# EBF31A_production_rev_3_1.net
KiCad netlist of a schematic drawn in EAGLE
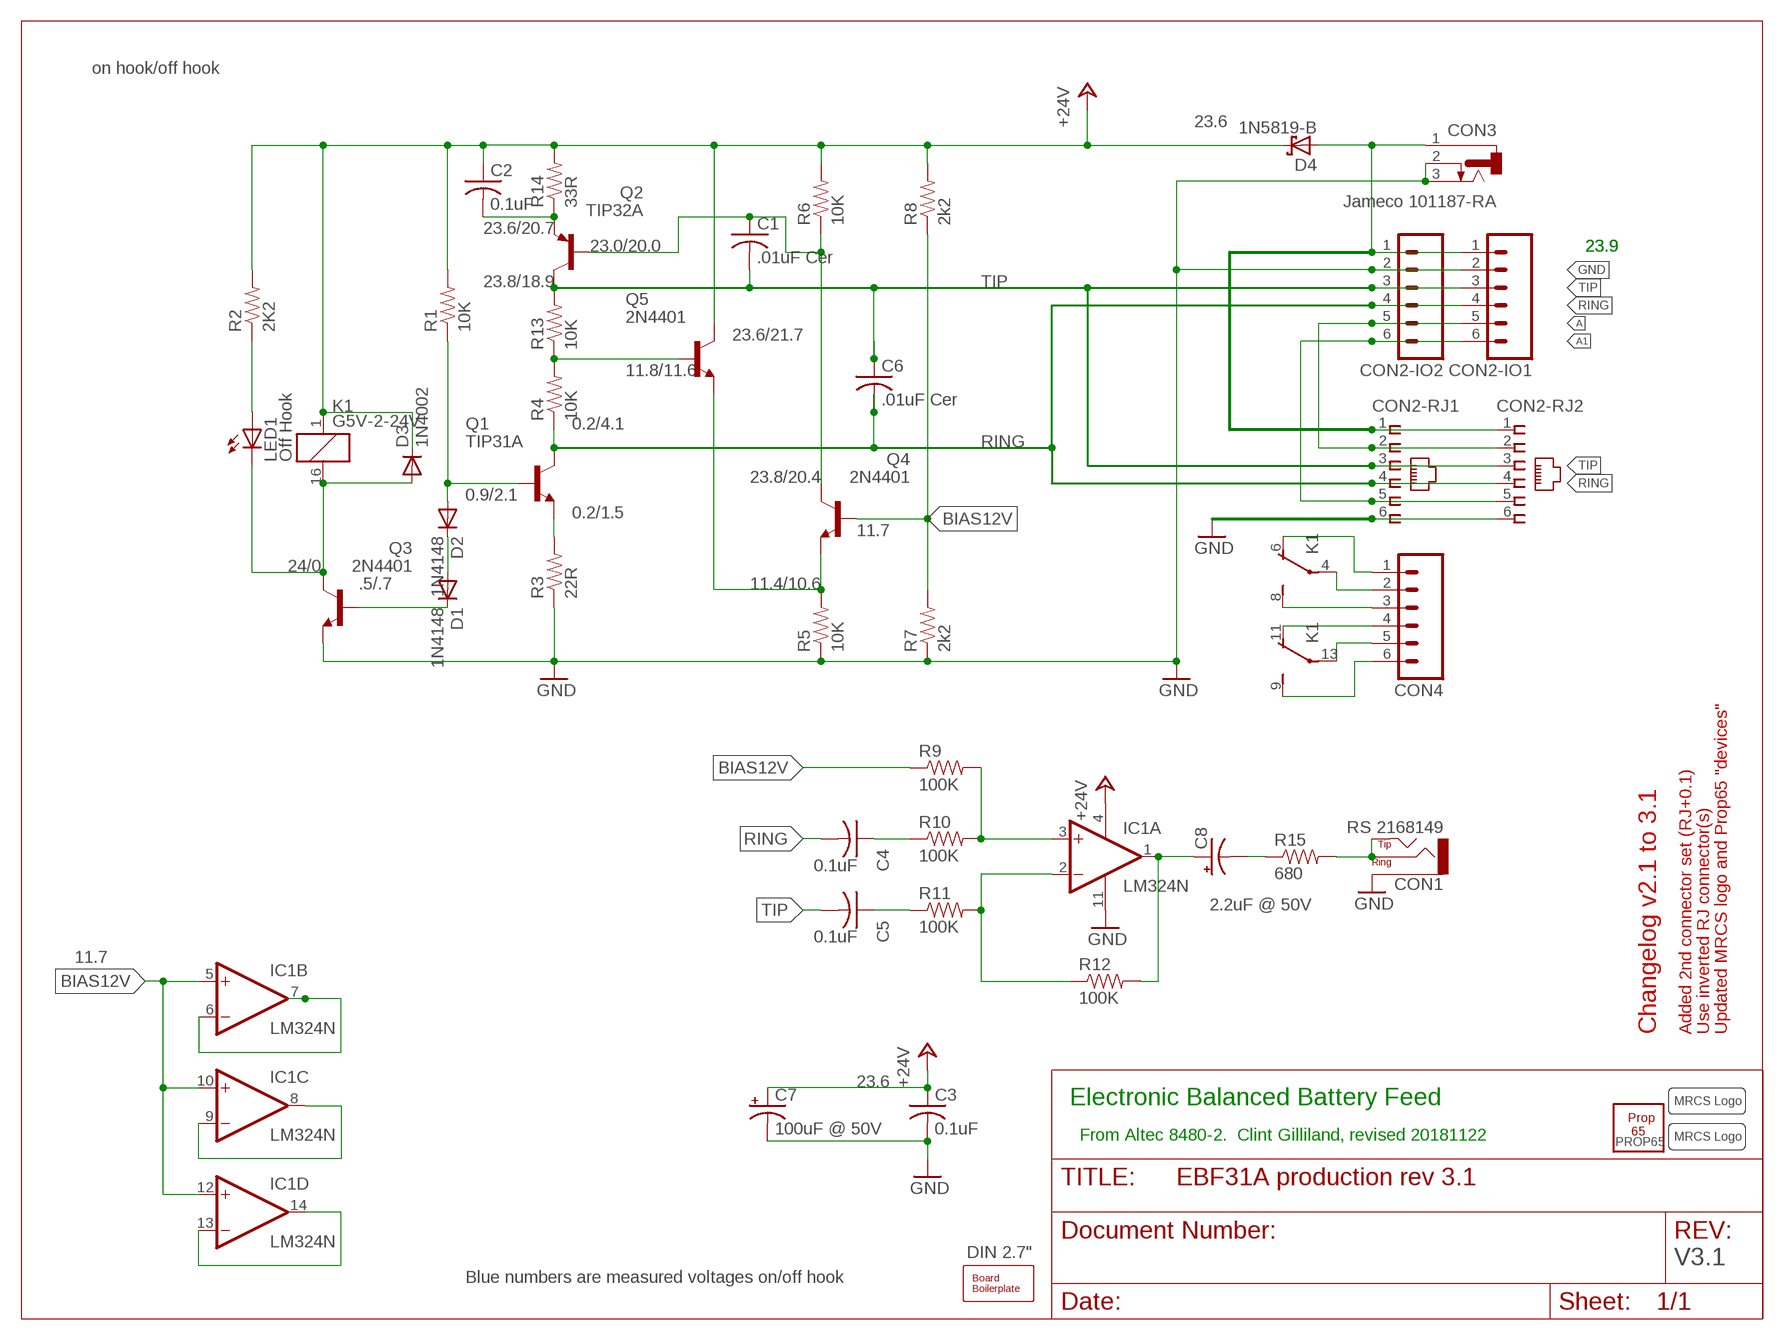
[diagram p0: schematic, sheet 1]

(export (version "E")
  (design (tool "Eeschema 10.0.6"))
  (components
    (comp (ref "C1")
      (value ".01uF Cer")
      (footprint "eagle-import:C025-030X050")
      (libsource (lib "eagle-import") (part "C-US025-030X050"))
    )
    (comp (ref "C2")
      (value "0.1uF")
      (footprint "eagle-import:C025-030X050")
      (libsource (lib "eagle-import") (part "C-US025-030X050"))
    )
    (comp (ref "C3")
      (value "0.1uF")
      (footprint "eagle-import:C025-030X050")
      (libsource (lib "eagle-import") (part "C-US025-030X050"))
    )
    (comp (ref "C4")
      (value "0.1uF")
      (footprint "eagle-import:C025-030X050")
      (libsource (lib "eagle-import") (part "C-US025-030X050"))
    )
    (comp (ref "C5")
      (value "0.1uF")
      (footprint "eagle-import:C025-030X050")
      (libsource (lib "eagle-import") (part "C-US025-030X050"))
    )
    (comp (ref "C6")
      (value ".01uF Cer")
      (footprint "eagle-import:C025-030X050")
      (libsource (lib "eagle-import") (part "C-US025-030X050"))
    )
    (comp (ref "C7")
      (value "100uF @ 50V")
      (footprint "eagle-import:E3,5-10")
      (libsource (lib "eagle-import") (part "CPOL-USE3.5-10"))
    )
    (comp (ref "C8")
      (value "2.2uF @ 50V")
      (footprint "eagle-import:E2-5")
      (libsource (lib "eagle-import") (part "CPOL-USE2-5"))
    )
    (comp (ref "CON1")
      (value "RS 2168149")
      (footprint "eagle-import:AUDIO-JACK-3.5MM_STEREO")
      (libsource (lib "eagle-import") (part "CONNECTOR-AUDIO3.5MM-ADAMTECH"))
    )
    (comp (ref "CON2-IO1")
      (value "M06FEMALE_LOCK")
      (footprint "eagle-import:1X06_FEMALE_LOCK.010")
      (libsource (lib "eagle-import") (part "M06FEMALE_LOCK"))
    )
    (comp (ref "CON2-IO2")
      (value "M06FEMALE_LOCK")
      (footprint "eagle-import:1X06_FEMALE_LOCK.010")
      (libsource (lib "eagle-import") (part "M06FEMALE_LOCK"))
    )
    (comp (ref "CON2-RJ1")
      (value "CONNECTOR-RJ25-43860-2-MOLEX")
      (footprint "eagle-import:RJ25-INVERTED")
      (libsource (lib "eagle-import") (part "CONNECTOR-RJ25-43860-2-MOLEX"))
    )
    (comp (ref "CON2-RJ2")
      (value "CONNECTOR-RJ25-43860-2-MOLEX")
      (footprint "eagle-import:RJ25-INVERTED")
      (libsource (lib "eagle-import") (part "CONNECTOR-RJ25-43860-2-MOLEX"))
    )
    (comp (ref "CON3")
      (value "Jameco 101187-RA")
      (footprint "eagle-import:DCJ0202")
      (libsource (lib "eagle-import") (part "CONNECTOR-DC-POWER-RA"))
    )
    (comp (ref "CON4")
      (value "M06FEMALE_LOCK")
      (footprint "eagle-import:1X06_FEMALE_LOCK.010")
      (libsource (lib "eagle-import") (part "M06FEMALE_LOCK"))
    )
    (comp (ref "D1")
      (value "1N4148")
      (footprint "eagle-import:DIODE-1N4148")
      (libsource (lib "eagle-import") (part "DIODE1N4148"))
    )
    (comp (ref "D2")
      (value "1N4148")
      (footprint "eagle-import:DIODE-1N4148")
      (libsource (lib "eagle-import") (part "DIODE1N4148"))
    )
    (comp (ref "D3")
      (value "1N4002")
      (footprint "eagle-import:DIODE-1N4148")
      (libsource (lib "eagle-import") (part "DIODE1N4148"))
    )
    (comp (ref "D4")
      (value "1N5819-B")
      (footprint "eagle-import:DO41-7.6")
      (libsource (lib "eagle-import") (part "1N5819-B"))
    )
    (comp (ref "IC1")
      (value "LM324N")
      (footprint "eagle-import:DIL14")
      (libsource (lib "eagle-import") (part "LM324N"))
    )
    (comp (ref "K1")
      (value "G5V-2-24V")
      (footprint "eagle-import:G5V-2")
      (fields (field (name "MPN") "G5V-2 5DC"))
      (libsource (lib "eagle-import") (part "G5V-2"))
    )
    (comp (ref "LED1")
      (value "Off Hook")
      (footprint "eagle-import:LED3MM")
      (libsource (lib "eagle-import") (part "LED3MM"))
    )
    (comp (ref "Q1")
      (value "TIP31A")
      (footprint "eagle-import:TO220")
      (libsource (lib "eagle-import") (part "TIP31C"))
    )
    (comp (ref "Q2")
      (value "TIP32A")
      (footprint "eagle-import:TO220")
      (libsource (lib "eagle-import") (part "TIP30"))
    )
    (comp (ref "Q3")
      (value "2N4401")
      (footprint "eagle-import:TO92-EBC")
      (libsource (lib "eagle-import") (part "-NPN-TO92-EBCBC317"))
    )
    (comp (ref "Q4")
      (value "2N4401")
      (footprint "eagle-import:TO92-EBC")
      (libsource (lib "eagle-import") (part "-NPN-TO92-EBCBC317"))
    )
    (comp (ref "Q5")
      (value "2N4401")
      (footprint "eagle-import:TO92-EBC")
      (libsource (lib "eagle-import") (part "-NPN-TO92-EBCBC317"))
    )
    (comp (ref "R1")
      (value "10K")
      (footprint "eagle-import:AXIAL-0.4")
      (libsource (lib "eagle-import") (part "RESISTORPTH-1/4W"))
    )
    (comp (ref "R2")
      (value "2K2")
      (footprint "eagle-import:AXIAL-0.4")
      (libsource (lib "eagle-import") (part "RESISTORPTH-1/4W"))
    )
    (comp (ref "R3")
      (value "22R")
      (footprint "eagle-import:AXIAL-0.4")
      (libsource (lib "eagle-import") (part "RESISTORPTH-1/4W"))
    )
    (comp (ref "R4")
      (value "10K")
      (footprint "eagle-import:AXIAL-0.4")
      (libsource (lib "eagle-import") (part "RESISTORPTH-1/4W"))
    )
    (comp (ref "R5")
      (value "10K")
      (footprint "eagle-import:AXIAL-0.4")
      (libsource (lib "eagle-import") (part "RESISTORPTH-1/4W"))
    )
    (comp (ref "R6")
      (value "10K")
      (footprint "eagle-import:AXIAL-0.4")
      (libsource (lib "eagle-import") (part "RESISTORPTH-1/4W"))
    )
    (comp (ref "R7")
      (value "2k2")
      (footprint "eagle-import:AXIAL-0.4")
      (libsource (lib "eagle-import") (part "RESISTORPTH-1/4W"))
    )
    (comp (ref "R8")
      (value "2k2")
      (footprint "eagle-import:AXIAL-0.4")
      (libsource (lib "eagle-import") (part "RESISTORPTH-1/4W"))
    )
    (comp (ref "R9")
      (value "100K")
      (footprint "eagle-import:AXIAL-0.4")
      (libsource (lib "eagle-import") (part "RESISTORPTH-1/4W"))
    )
    (comp (ref "R10")
      (value "100K")
      (footprint "eagle-import:AXIAL-0.4")
      (libsource (lib "eagle-import") (part "RESISTORPTH-1/4W"))
    )
    (comp (ref "R11")
      (value "100K")
      (footprint "eagle-import:AXIAL-0.4")
      (libsource (lib "eagle-import") (part "RESISTORPTH-1/4W"))
    )
    (comp (ref "R12")
      (value "100K")
      (footprint "eagle-import:AXIAL-0.4")
      (libsource (lib "eagle-import") (part "RESISTORPTH-1/4W"))
    )
    (comp (ref "R13")
      (value "10K")
      (footprint "eagle-import:AXIAL-0.4")
      (libsource (lib "eagle-import") (part "RESISTORPTH-1/4W"))
    )
    (comp (ref "R14")
      (value "33R")
      (footprint "eagle-import:AXIAL-0.4")
      (libsource (lib "eagle-import") (part "RESISTORPTH-1/4W"))
    )
    (comp (ref "R15")
      (value "680")
      (footprint "eagle-import:AXIAL-0.4")
      (libsource (lib "eagle-import") (part "RESISTORPTH-1/4W"))
    )
    (comp (ref "U$1")
      (value "BOARD")
      (footprint "eagle-import:BOARD-DINRAIL-2.71IN-MRCS")
      (libsource (lib "eagle-import") (part "BOARD69X100MRCS"))
    )
    (comp (ref "U$2")
      (value "MRCS-LOGOBOT-LARGE")
      (footprint "eagle-import:MRCS-LOGO")
      (libsource (lib "eagle-import") (part "MRCS-LOGOBOT-LARGE"))
    )
    (comp (ref "U$3")
      (value "MRCS-LOGOBOT-LARGE")
      (footprint "eagle-import:MRCS-LOGO")
      (libsource (lib "eagle-import") (part "MRCS-LOGOBOT-LARGE"))
    )
    (comp (ref "U$4")
      (value "PROP65")
      (footprint "eagle-import:PROP65")
      (libsource (lib "eagle-import") (part "PROP65"))
    )
  )
  (nets
    (net (code "1") (name "+24V") (class "Default")
      (node (ref "C2") (pin "1") (pinfunction "1_1") (pintype "passive"))
      (node (ref "C3") (pin "1") (pinfunction "1_1") (pintype "passive"))
      (node (ref "C7") (pin "+") (pinfunction "+_+") (pintype "passive"))
      (node (ref "D3") (pin "C") (pinfunction "C_C") (pintype "passive"))
      (node (ref "D4") (pin "C") (pinfunction "C_C") (pintype "passive"))
      (node (ref "IC1") (pin "4") (pinfunction "V+_4") (pintype "power_in"))
      (node (ref "K1") (pin "1") (pinfunction "1_1") (pintype "passive"))
      (node (ref "Q5") (pin "C") (pinfunction "C_C") (pintype "passive"))
      (node (ref "R1") (pin "P$2") (pinfunction "2_P$2") (pintype "passive"))
      (node (ref "R14") (pin "P$2") (pinfunction "2_P$2") (pintype "passive"))
      (node (ref "R2") (pin "P$2") (pinfunction "2_P$2") (pintype "passive"))
      (node (ref "R6") (pin "P$2") (pinfunction "2_P$2") (pintype "passive"))
      (node (ref "R8") (pin "P$2") (pinfunction "2_P$2") (pintype "passive"))
    )
    (net (code "2") (name "A") (class "Default")
      (node (ref "CON2-IO1") (pin "5") (pinfunction "5_5") (pintype "passive"))
      (node (ref "CON2-IO2") (pin "5") (pinfunction "5_5") (pintype "passive"))
      (node (ref "CON2-RJ1") (pin "2") (pinfunction "2_2") (pintype "passive"))
      (node (ref "CON2-RJ2") (pin "2") (pinfunction "2_2") (pintype "passive"))
    )
    (net (code "3") (name "A1") (class "Default")
      (node (ref "CON2-IO1") (pin "6") (pinfunction "6_6") (pintype "passive"))
      (node (ref "CON2-IO2") (pin "6") (pinfunction "6_6") (pintype "passive"))
      (node (ref "CON2-RJ1") (pin "5") (pinfunction "5_5") (pintype "passive"))
      (node (ref "CON2-RJ2") (pin "5") (pinfunction "5_5") (pintype "passive"))
    )
    (net (code "4") (name "BIAS12V") (class "Default")
      (node (ref "IC1") (pin "10") (pinfunction "+IN_10") (pintype "input"))
      (node (ref "IC1") (pin "12") (pinfunction "+IN_12") (pintype "input"))
      (node (ref "IC1") (pin "5") (pinfunction "+IN_5") (pintype "input"))
      (node (ref "Q4") (pin "B") (pinfunction "B_B") (pintype "passive"))
      (node (ref "R7") (pin "P$2") (pinfunction "2_P$2") (pintype "passive"))
      (node (ref "R8") (pin "P$1") (pinfunction "1_P$1") (pintype "passive"))
      (node (ref "R9") (pin "P$1") (pinfunction "1_P$1") (pintype "passive"))
    )
    (net (code "5") (name "GND") (class "Default")
      (node (ref "C3") (pin "2") (pinfunction "2_2") (pintype "passive"))
      (node (ref "C7") (pin "-") (pinfunction "-_-") (pintype "passive"))
      (node (ref "CON1") (pin "GND") (pinfunction "SLEEVE_GND") (pintype "bidirectional"))
      (node (ref "CON2-IO1") (pin "2") (pinfunction "2_2") (pintype "passive"))
      (node (ref "CON2-IO2") (pin "2") (pinfunction "2_2") (pintype "passive"))
      (node (ref "CON2-RJ1") (pin "6") (pinfunction "6_6") (pintype "passive"))
      (node (ref "CON2-RJ2") (pin "6") (pinfunction "6_6") (pintype "passive"))
      (node (ref "CON3") (pin "2") (pinfunction "2_2") (pintype "passive"))
      (node (ref "CON3") (pin "3") (pinfunction "3_3") (pintype "passive"))
      (node (ref "IC1") (pin "11") (pinfunction "V-_11") (pintype "power_in"))
      (node (ref "Q3") (pin "E") (pinfunction "E_E") (pintype "passive"))
      (node (ref "R3") (pin "P$1") (pinfunction "1_P$1") (pintype "passive"))
      (node (ref "R5") (pin "P$1") (pinfunction "1_P$1") (pintype "passive"))
      (node (ref "R7") (pin "P$1") (pinfunction "1_P$1") (pintype "passive"))
    )
    (net (code "6") (name "Net-(CON2-IO1-Pad1)") (class "Default")
      (node (ref "CON2-IO1") (pin "1") (pinfunction "1_1") (pintype "passive"))
      (node (ref "CON2-IO2") (pin "1") (pinfunction "1_1") (pintype "passive"))
      (node (ref "CON2-RJ1") (pin "1") (pinfunction "1_1") (pintype "passive"))
      (node (ref "CON2-RJ2") (pin "1") (pinfunction "1_1") (pintype "passive"))
      (node (ref "CON3") (pin "1") (pinfunction "1_1") (pintype "passive"))
      (node (ref "D4") (pin "A") (pinfunction "A_A") (pintype "passive"))
    )
    (net (code "7") (name "Net-(D1-PadA)") (class "Default")
      (node (ref "D1") (pin "A") (pinfunction "A_A") (pintype "passive"))
      (node (ref "D2") (pin "C") (pinfunction "C_C") (pintype "passive"))
    )
    (net (code "8") (name "Net-(D1-PadC)") (class "Default")
      (node (ref "D1") (pin "C") (pinfunction "C_C") (pintype "passive"))
      (node (ref "Q3") (pin "B") (pinfunction "B_B") (pintype "passive"))
    )
    (net (code "9") (name "Net-(IC1A-+IN)") (class "Default")
      (node (ref "IC1") (pin "3") (pinfunction "+IN_3") (pintype "input"))
      (node (ref "R10") (pin "P$2") (pinfunction "2_P$2") (pintype "passive"))
      (node (ref "R9") (pin "P$2") (pinfunction "2_P$2") (pintype "passive"))
    )
    (net (code "10") (name "Net-(IC1A--IN)") (class "Default")
      (node (ref "IC1") (pin "2") (pinfunction "-IN_2") (pintype "input"))
      (node (ref "R11") (pin "P$2") (pinfunction "2_P$2") (pintype "passive"))
      (node (ref "R12") (pin "P$1") (pinfunction "1_P$1") (pintype "passive"))
    )
    (net (code "11") (name "Net-(IC1A-OUT)") (class "Default")
      (node (ref "C8") (pin "+") (pinfunction "+_+") (pintype "passive"))
      (node (ref "IC1") (pin "1") (pinfunction "OUT_1") (pintype "output"))
      (node (ref "R12") (pin "P$2") (pinfunction "2_P$2") (pintype "passive"))
    )
    (net (code "12") (name "Net-(IC1B--IN)") (class "Default")
      (node (ref "IC1") (pin "6") (pinfunction "-IN_6") (pintype "input"))
      (node (ref "IC1") (pin "7") (pinfunction "OUT_7") (pintype "output"))
    )
    (net (code "13") (name "Net-(IC1C--IN)") (class "Default")
      (node (ref "IC1") (pin "8") (pinfunction "OUT_8") (pintype "output"))
      (node (ref "IC1") (pin "9") (pinfunction "-IN_9") (pintype "input"))
    )
    (net (code "14") (name "Net-(IC1D--IN)") (class "Default")
      (node (ref "IC1") (pin "13") (pinfunction "-IN_13") (pintype "input"))
      (node (ref "IC1") (pin "14") (pinfunction "OUT_14") (pintype "output"))
    )
    (net (code "15") (name "Net-(K1A-O)") (class "Default")
      (node (ref "CON4") (pin "1") (pinfunction "1_1") (pintype "passive"))
      (node (ref "K1") (pin "6") (pinfunction "O_6") (pintype "passive"))
    )
    (net (code "16") (name "Net-(K1A-P)") (class "Default")
      (node (ref "CON4") (pin "2") (pinfunction "2_2") (pintype "passive"))
      (node (ref "K1") (pin "4") (pinfunction "P_4") (pintype "passive"))
    )
    (net (code "17") (name "Net-(K1A-S)") (class "Default")
      (node (ref "CON4") (pin "3") (pinfunction "3_3") (pintype "passive"))
      (node (ref "K1") (pin "8") (pinfunction "S_8") (pintype "passive"))
    )
    (net (code "18") (name "Net-(K1B-O)") (class "Default")
      (node (ref "CON4") (pin "4") (pinfunction "4_4") (pintype "passive"))
      (node (ref "K1") (pin "11") (pinfunction "O_11") (pintype "passive"))
    )
    (net (code "19") (name "Net-(K1B-P)") (class "Default")
      (node (ref "CON4") (pin "5") (pinfunction "5_5") (pintype "passive"))
      (node (ref "K1") (pin "13") (pinfunction "P_13") (pintype "passive"))
    )
    (net (code "20") (name "Net-(K1B-S)") (class "Default")
      (node (ref "CON4") (pin "6") (pinfunction "6_6") (pintype "passive"))
      (node (ref "K1") (pin "9") (pinfunction "S_9") (pintype "passive"))
    )
    (net (code "21") (name "Net-(K1C-2)") (class "Default")
      (node (ref "D3") (pin "A") (pinfunction "A_A") (pintype "passive"))
      (node (ref "K1") (pin "16") (pinfunction "2_16") (pintype "passive"))
      (node (ref "LED1") (pin "K") (pinfunction "C_K") (pintype "passive"))
      (node (ref "Q3") (pin "C") (pinfunction "C_C") (pintype "passive"))
    )
    (net (code "22") (name "Net-(Q1-B)") (class "Default")
      (node (ref "D2") (pin "A") (pinfunction "A_A") (pintype "passive"))
      (node (ref "Q1") (pin "1") (pinfunction "B_1") (pintype "passive"))
      (node (ref "R1") (pin "P$1") (pinfunction "1_P$1") (pintype "passive"))
    )
    (net (code "23") (name "Net-(Q1-E)") (class "Default")
      (node (ref "Q1") (pin "3") (pinfunction "E_3") (pintype "passive"))
      (node (ref "R3") (pin "P$2") (pinfunction "2_P$2") (pintype "passive"))
    )
    (net (code "24") (name "Net-(Q2-B)") (class "Default")
      (node (ref "C1") (pin "1") (pinfunction "1_1") (pintype "passive"))
      (node (ref "Q2") (pin "1") (pinfunction "B_1") (pintype "passive"))
      (node (ref "Q4") (pin "C") (pinfunction "C_C") (pintype "passive"))
      (node (ref "R6") (pin "P$1") (pinfunction "1_P$1") (pintype "passive"))
    )
    (net (code "25") (name "Net-(Q2-E)") (class "Default")
      (node (ref "C2") (pin "2") (pinfunction "2_2") (pintype "passive"))
      (node (ref "Q2") (pin "3") (pinfunction "E_3") (pintype "passive"))
      (node (ref "R14") (pin "P$1") (pinfunction "1_P$1") (pintype "passive"))
    )
    (net (code "26") (name "Net-(R2-1)") (class "Default")
      (node (ref "LED1") (pin "A") (pinfunction "A_A") (pintype "passive"))
      (node (ref "R2") (pin "P$1") (pinfunction "1_P$1") (pintype "passive"))
    )
    (net (code "27") (name "Net-(R5-2)") (class "Default")
      (node (ref "Q4") (pin "E") (pinfunction "E_E") (pintype "passive"))
      (node (ref "Q5") (pin "E") (pinfunction "E_E") (pintype "passive"))
      (node (ref "R5") (pin "P$2") (pinfunction "2_P$2") (pintype "passive"))
    )
    (net (code "28") (name "Net-(R10-1)") (class "Default")
      (node (ref "C4") (pin "1") (pinfunction "1_1") (pintype "passive"))
      (node (ref "R10") (pin "P$1") (pinfunction "1_P$1") (pintype "passive"))
    )
    (net (code "29") (name "Net-(R11-1)") (class "Default")
      (node (ref "C5") (pin "1") (pinfunction "1_1") (pintype "passive"))
      (node (ref "R11") (pin "P$1") (pinfunction "1_P$1") (pintype "passive"))
    )
    (net (code "30") (name "Net-(R13-1)") (class "Default")
      (node (ref "Q5") (pin "B") (pinfunction "B_B") (pintype "passive"))
      (node (ref "R13") (pin "P$1") (pinfunction "1_P$1") (pintype "passive"))
      (node (ref "R4") (pin "P$2") (pinfunction "2_P$2") (pintype "passive"))
    )
    (net (code "31") (name "Net-(R15-1)") (class "Default")
      (node (ref "C8") (pin "-") (pinfunction "-_-") (pintype "passive"))
      (node (ref "R15") (pin "P$1") (pinfunction "1_P$1") (pintype "passive"))
    )
    (net (code "32") (name "Net-(R15-2)") (class "Default")
      (node (ref "CON1") (pin "RING") (pinfunction "RING_RING") (pintype "bidirectional"))
      (node (ref "CON1") (pin "TIP") (pinfunction "TIP_TIP") (pintype "bidirectional"))
      (node (ref "R15") (pin "P$2") (pinfunction "2_P$2") (pintype "passive"))
    )
    (net (code "33") (name "RING") (class "Default")
      (node (ref "C4") (pin "2") (pinfunction "2_2") (pintype "passive"))
      (node (ref "C6") (pin "2") (pinfunction "2_2") (pintype "passive"))
      (node (ref "CON2-IO1") (pin "4") (pinfunction "4_4") (pintype "passive"))
      (node (ref "CON2-IO2") (pin "4") (pinfunction "4_4") (pintype "passive"))
      (node (ref "CON2-RJ1") (pin "4") (pinfunction "4_4") (pintype "passive"))
      (node (ref "CON2-RJ2") (pin "4") (pinfunction "4_4") (pintype "passive"))
      (node (ref "Q1") (pin "2") (pinfunction "C_2") (pintype "passive"))
      (node (ref "R4") (pin "P$1") (pinfunction "1_P$1") (pintype "passive"))
    )
    (net (code "34") (name "TIP") (class "Default")
      (node (ref "C1") (pin "2") (pinfunction "2_2") (pintype "passive"))
      (node (ref "C5") (pin "2") (pinfunction "2_2") (pintype "passive"))
      (node (ref "C6") (pin "1") (pinfunction "1_1") (pintype "passive"))
      (node (ref "CON2-IO1") (pin "3") (pinfunction "3_3") (pintype "passive"))
      (node (ref "CON2-IO2") (pin "3") (pinfunction "3_3") (pintype "passive"))
      (node (ref "CON2-RJ1") (pin "3") (pinfunction "3_3") (pintype "passive"))
      (node (ref "CON2-RJ2") (pin "3") (pinfunction "3_3") (pintype "passive"))
      (node (ref "Q2") (pin "2") (pinfunction "C_2") (pintype "passive"))
      (node (ref "R13") (pin "P$2") (pinfunction "2_P$2") (pintype "passive"))
    )
  )
)
